# PowerMergeBoard.net
KiCad netlist of a schematic drawn in Altium Designer
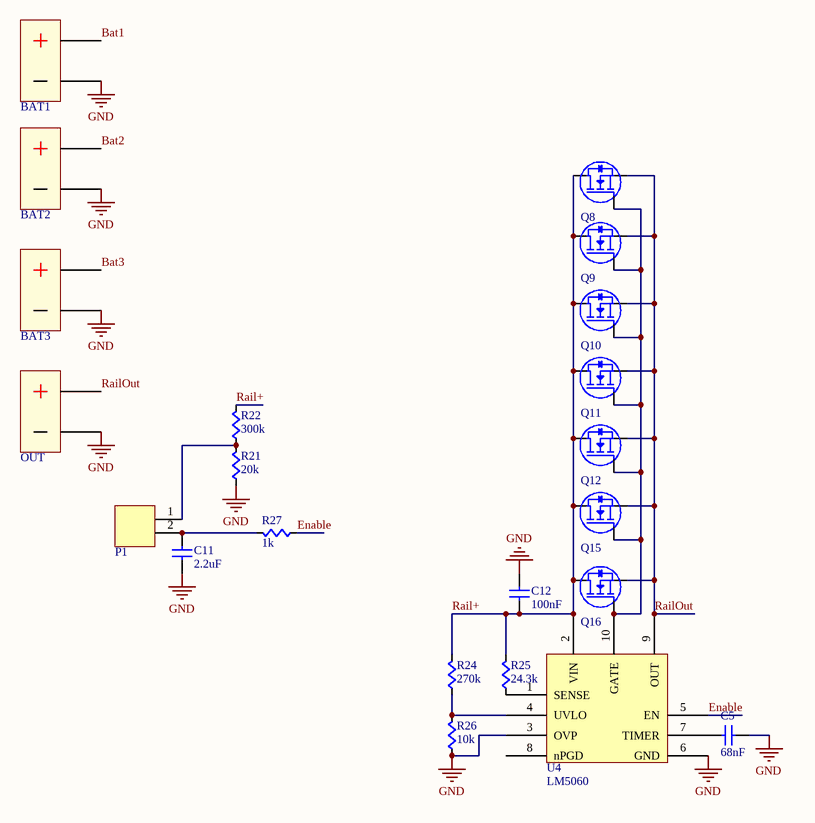
[diagram p0: PowerMergeBoard.SchDoc]

(export (version "E")
  (design (tool "Eeschema 10.0.6"))
  (components
    (comp (ref "BAT1")
      (value "BATWIRE")
      (footprint "BATWIRE10")
      (description "Two large gauge leads soldered directly to the board.")
      (libsource (lib "Connectors") (part "BATWIRE"))
    )
    (comp (ref "BAT2")
      (value "BATWIRE")
      (footprint "BATWIRE10")
      (description "Two large gauge leads soldered directly to the board.")
      (libsource (lib "Connectors") (part "BATWIRE"))
    )
    (comp (ref "BAT3")
      (value "BATWIRE")
      (footprint "BATWIRE10")
      (description "Two large gauge leads soldered directly to the board.")
      (libsource (lib "Connectors") (part "BATWIRE"))
    )
    (comp (ref "C5")
      (value "68nF")
      (footprint "CAPC0603")
      (fields (field (name "Comment") "Cap"))
      (libsource (lib "SubjuGator8") (part "Cap"))
    )
    (comp (ref "C11")
      (value "2.2uF")
      (footprint "CAPC1206")
      (fields (field (name "Comment") "Cap"))
      (libsource (lib "SubjuGator8") (part "Cap"))
    )
    (comp (ref "C12")
      (value "100nF")
      (footprint "CAPC0603")
      (fields (field (name "Comment") "Cap"))
      (libsource (lib "SubjuGator8") (part "Cap"))
    )
    (comp (ref "OUT")
      (value "BATWIRE")
      (footprint "BATWIRE10")
      (description "Two large gauge leads soldered directly to the board.")
      (libsource (lib "Connectors") (part "BATWIRE"))
    )
    (comp (ref "P1")
      (value "2-pin Vert Sherlock")
      (footprint "MOLEX-HDR-1X2-SHERLOCK-VERT")
      (libsource (lib "SubjuGator8") (part "MOLEX-HDR-1x2-SHERLOCK_VERT"))
    )
    (comp (ref "Q8")
      (value "CSD19502Q5B")
      (footprint "CSD19502Q5B")
      (description "NEXFET Power MOSFET")
      (libsource (lib "SubjuGator8") (part "CSD19502Q5B"))
    )
    (comp (ref "Q9")
      (value "CSD19502Q5B")
      (footprint "CSD19502Q5B")
      (description "NEXFET Power MOSFET")
      (libsource (lib "SubjuGator8") (part "CSD19502Q5B"))
    )
    (comp (ref "Q10")
      (value "CSD19502Q5B")
      (footprint "CSD19502Q5B")
      (description "NEXFET Power MOSFET")
      (libsource (lib "SubjuGator8") (part "CSD19502Q5B"))
    )
    (comp (ref "Q11")
      (value "CSD19502Q5B")
      (footprint "CSD19502Q5B")
      (description "NEXFET Power MOSFET")
      (libsource (lib "SubjuGator8") (part "CSD19502Q5B"))
    )
    (comp (ref "Q12")
      (value "CSD19502Q5B")
      (footprint "CSD19502Q5B")
      (description "NEXFET Power MOSFET")
      (libsource (lib "SubjuGator8") (part "CSD19502Q5B"))
    )
    (comp (ref "Q15")
      (value "CSD19502Q5B")
      (footprint "CSD19502Q5B")
      (description "NEXFET Power MOSFET")
      (libsource (lib "SubjuGator8") (part "CSD19502Q5B"))
    )
    (comp (ref "Q16")
      (value "CSD19502Q5B")
      (footprint "CSD19502Q5B")
      (description "NEXFET Power MOSFET")
      (libsource (lib "SubjuGator8") (part "CSD19502Q5B"))
    )
    (comp (ref "R21")
      (value "20k")
      (footprint "RES0603")
      (fields (field (name "Comment") "Res"))
      (libsource (lib "SubjuGator8") (part "Res"))
    )
    (comp (ref "R22")
      (value "300k")
      (footprint "RES0603")
      (fields (field (name "Comment") "Res"))
      (libsource (lib "SubjuGator8") (part "Res"))
    )
    (comp (ref "R24")
      (value "270k")
      (footprint "RES0603")
      (fields (field (name "Comment") "Res"))
      (libsource (lib "SubjuGator8") (part "Res"))
    )
    (comp (ref "R25")
      (value "24.3k")
      (footprint "RES0603")
      (fields (field (name "Comment") "Res"))
      (libsource (lib "SubjuGator8") (part "Res"))
    )
    (comp (ref "R26")
      (value "10k")
      (footprint "RES0603")
      (fields (field (name "Comment") "Res"))
      (libsource (lib "SubjuGator8") (part "Res"))
    )
    (comp (ref "R27")
      (value "1k")
      (footprint "RES0603")
      (fields (field (name "Comment") "Res"))
      (libsource (lib "SubjuGator8") (part "Res"))
    )
    (comp (ref "U4")
      (value "LM5060")
      (footprint "LM5060")
      (description "Hotswap Controller")
      (libsource (lib "SubjuGator8") (part "LM5060"))
    )
  )
  (nets
    (net (code "1") (name "/Bat1") (class "Default")
      (node (ref "BAT1") (pin "+") (pinfunction "+_+") (pintype "power_in"))
    )
    (net (code "2") (name "/Bat2") (class "Default")
      (node (ref "BAT2") (pin "+") (pinfunction "+_+") (pintype "power_in"))
    )
    (net (code "3") (name "/Bat3") (class "Default")
      (node (ref "BAT3") (pin "+") (pinfunction "+_+") (pintype "power_in"))
    )
    (net (code "4") (name "/Enable") (class "Default")
      (node (ref "R27") (pin "2") (pinfunction "B_2") (pintype "passive"))
      (node (ref "U4") (pin "5") (pinfunction "EN_5") (pintype "passive"))
    )
    (net (code "5") (name "/Rail+") (class "Default")
      (node (ref "C12") (pin "2") (pinfunction "B_2") (pintype "passive"))
      (node (ref "Q10") (pin "D") (pinfunction "D_D") (pintype "passive"))
      (node (ref "Q11") (pin "D") (pinfunction "D_D") (pintype "passive"))
      (node (ref "Q12") (pin "D") (pinfunction "D_D") (pintype "passive"))
      (node (ref "Q15") (pin "D") (pinfunction "D_D") (pintype "passive"))
      (node (ref "Q16") (pin "D") (pinfunction "D_D") (pintype "passive"))
      (node (ref "Q8") (pin "D") (pinfunction "D_D") (pintype "passive"))
      (node (ref "Q9") (pin "D") (pinfunction "D_D") (pintype "passive"))
      (node (ref "R22") (pin "1") (pinfunction "A_1") (pintype "passive"))
      (node (ref "R24") (pin "1") (pinfunction "A_1") (pintype "passive"))
      (node (ref "R25") (pin "1") (pinfunction "A_1") (pintype "passive"))
      (node (ref "U4") (pin "2") (pinfunction "VIN_2") (pintype "passive"))
    )
    (net (code "6") (name "/RailOut") (class "Default")
      (node (ref "OUT") (pin "+") (pinfunction "+_+") (pintype "power_in"))
      (node (ref "Q10") (pin "S") (pinfunction "S_S") (pintype "passive"))
      (node (ref "Q11") (pin "S") (pinfunction "S_S") (pintype "passive"))
      (node (ref "Q12") (pin "S") (pinfunction "S_S") (pintype "passive"))
      (node (ref "Q15") (pin "S") (pinfunction "S_S") (pintype "passive"))
      (node (ref "Q16") (pin "S") (pinfunction "S_S") (pintype "passive"))
      (node (ref "Q8") (pin "S") (pinfunction "S_S") (pintype "passive"))
      (node (ref "Q9") (pin "S") (pinfunction "S_S") (pintype "passive"))
      (node (ref "U4") (pin "9") (pinfunction "OUT_9") (pintype "passive"))
    )
    (net (code "7") (name "GND") (class "Default")
      (node (ref "BAT1") (pin "-") (pinfunction "-_-") (pintype "power_in"))
      (node (ref "BAT2") (pin "-") (pinfunction "-_-") (pintype "power_in"))
      (node (ref "BAT3") (pin "-") (pinfunction "-_-") (pintype "power_in"))
      (node (ref "C11") (pin "2") (pinfunction "B_2") (pintype "passive"))
      (node (ref "C12") (pin "1") (pinfunction "A_1") (pintype "passive"))
      (node (ref "C5") (pin "2") (pinfunction "B_2") (pintype "passive"))
      (node (ref "OUT") (pin "-") (pinfunction "-_-") (pintype "power_in"))
      (node (ref "R21") (pin "2") (pinfunction "B_2") (pintype "passive"))
      (node (ref "R26") (pin "2") (pinfunction "B_2") (pintype "passive"))
      (node (ref "U4") (pin "3") (pinfunction "OVP_3") (pintype "passive"))
      (node (ref "U4") (pin "6") (pinfunction "GND_6") (pintype "passive"))
    )
    (net (code "8") (name "Net-(C5-A)") (class "Default")
      (node (ref "C5") (pin "1") (pinfunction "A_1") (pintype "passive"))
      (node (ref "U4") (pin "7") (pinfunction "TIMER_7") (pintype "passive"))
    )
    (net (code "9") (name "Net-(C11-A)") (class "Default")
      (node (ref "C11") (pin "1") (pinfunction "A_1") (pintype "passive"))
      (node (ref "P1") (pin "2") (pinfunction "2_2") (pintype "passive"))
      (node (ref "R27") (pin "1") (pinfunction "A_1") (pintype "passive"))
    )
    (net (code "10") (name "Net-(R21-A)") (class "Default")
      (node (ref "P1") (pin "1") (pinfunction "1_1") (pintype "passive"))
      (node (ref "R21") (pin "1") (pinfunction "A_1") (pintype "passive"))
      (node (ref "R22") (pin "2") (pinfunction "B_2") (pintype "passive"))
    )
    (net (code "11") (name "Net-(R24-B)") (class "Default")
      (node (ref "R24") (pin "2") (pinfunction "B_2") (pintype "passive"))
      (node (ref "R26") (pin "1") (pinfunction "A_1") (pintype "passive"))
      (node (ref "U4") (pin "4") (pinfunction "UVLO_4") (pintype "passive"))
    )
    (net (code "12") (name "Net-(R25-B)") (class "Default")
      (node (ref "R25") (pin "2") (pinfunction "B_2") (pintype "passive"))
      (node (ref "U4") (pin "1") (pinfunction "SENSE_1") (pintype "passive"))
    )
    (net (code "13") (name "Net-(U4-GATE)") (class "Default")
      (node (ref "Q10") (pin "G") (pinfunction "G_G") (pintype "passive"))
      (node (ref "Q11") (pin "G") (pinfunction "G_G") (pintype "passive"))
      (node (ref "Q12") (pin "G") (pinfunction "G_G") (pintype "passive"))
      (node (ref "Q15") (pin "G") (pinfunction "G_G") (pintype "passive"))
      (node (ref "Q16") (pin "G") (pinfunction "G_G") (pintype "passive"))
      (node (ref "Q8") (pin "G") (pinfunction "G_G") (pintype "passive"))
      (node (ref "Q9") (pin "G") (pinfunction "G_G") (pintype "passive"))
      (node (ref "U4") (pin "10") (pinfunction "GATE_10") (pintype "passive"))
    )
    (net (code "14") (name "unconnected-(U4-nPGD-Pad8)") (class "Default")
      (node (ref "U4") (pin "8") (pinfunction "nPGD_8") (pintype "passive"))
    )
  )
)
